# Pi2c.net
KiCad netlist of a schematic drawn in EAGLE
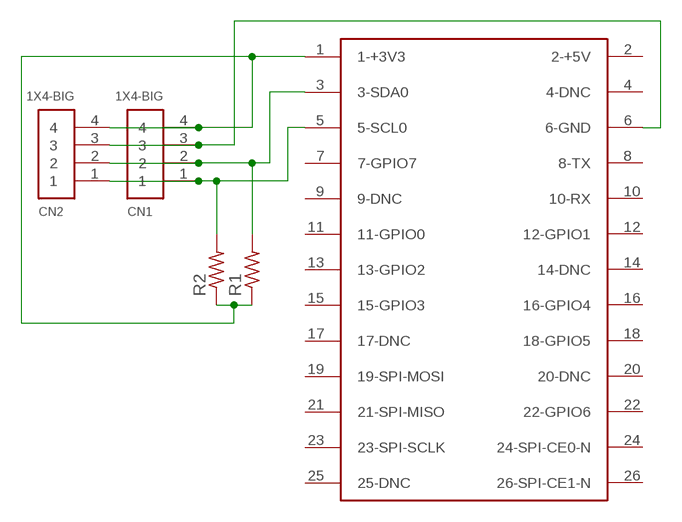
[diagram p0: schematic, sheet 1]

(export (version "E")
  (design (tool "Eeschema 10.0.6"))
  (components
    (comp (ref "CN1")
      (value "1X4-BIG")
      (footprint "eagle-import:1X04-BIG")
      (libsource (lib "eagle-import") (part "1X4-BIG"))
    )
    (comp (ref "CN2")
      (value "1X4-BIG")
      (footprint "eagle-import:1X04-BIG")
      (libsource (lib "eagle-import") (part "1X4-BIG"))
    )
    (comp (ref "R1")
      (value "R-US_0207/7")
      (footprint "eagle-import:0207_7")
      (libsource (lib "eagle-import") (part "R-US_0207/7"))
    )
    (comp (ref "R2")
      (value "R-US_0207/7")
      (footprint "eagle-import:0207_7")
      (libsource (lib "eagle-import") (part "R-US_0207/7"))
    )
    (comp (ref "U$1")
      (value "RASPBERRY-PI")
      (footprint "eagle-import:RASPBERRY-PI")
      (libsource (lib "eagle-import") (part "RASPBERRY-PI"))
    )
  )
  (nets
    (net (code "1") (name "Net-(U$1-1-+3V3)") (class "Default")
      (node (ref "CN1") (pin "4") (pinfunction "4_4") (pintype "bidirectional"))
      (node (ref "CN2") (pin "4") (pinfunction "4_4") (pintype "bidirectional"))
      (node (ref "R1") (pin "1") (pinfunction "1_1") (pintype "passive"))
      (node (ref "R2") (pin "1") (pinfunction "1_1") (pintype "passive"))
      (node (ref "U$1") (pin "1") (pinfunction "1-+3V3_1") (pintype "bidirectional"))
    )
    (net (code "2") (name "Net-(U$1-3-SDA0)") (class "Default")
      (node (ref "CN1") (pin "2") (pinfunction "2_2") (pintype "bidirectional"))
      (node (ref "CN2") (pin "2") (pinfunction "2_2") (pintype "bidirectional"))
      (node (ref "R1") (pin "2") (pinfunction "2_2") (pintype "passive"))
      (node (ref "U$1") (pin "3") (pinfunction "3-SDA0_3") (pintype "bidirectional"))
    )
    (net (code "3") (name "Net-(U$1-5-SCL0)") (class "Default")
      (node (ref "CN1") (pin "1") (pinfunction "1_1") (pintype "bidirectional"))
      (node (ref "CN2") (pin "1") (pinfunction "1_1") (pintype "bidirectional"))
      (node (ref "R2") (pin "2") (pinfunction "2_2") (pintype "passive"))
      (node (ref "U$1") (pin "5") (pinfunction "5-SCL0_5") (pintype "bidirectional"))
    )
    (net (code "4") (name "Net-(U$1-6-GND)") (class "Default")
      (node (ref "CN1") (pin "3") (pinfunction "3_3") (pintype "bidirectional"))
      (node (ref "CN2") (pin "3") (pinfunction "3_3") (pintype "bidirectional"))
      (node (ref "U$1") (pin "6") (pinfunction "6-GND_6") (pintype "bidirectional"))
    )
    (net (code "5") (name "unconnected-(U$1-2-+5V-Pad2)") (class "Default")
      (node (ref "U$1") (pin "2") (pinfunction "2-+5V_2") (pintype "bidirectional"))
    )
    (net (code "6") (name "unconnected-(U$1-4-DNC-Pad4)") (class "Default")
      (node (ref "U$1") (pin "4") (pinfunction "4-DNC_4") (pintype "bidirectional"))
    )
    (net (code "7") (name "unconnected-(U$1-7-GPIO7-Pad7)") (class "Default")
      (node (ref "U$1") (pin "7") (pinfunction "7-GPIO7_7") (pintype "bidirectional"))
    )
    (net (code "8") (name "unconnected-(U$1-8-TX-Pad8)") (class "Default")
      (node (ref "U$1") (pin "8") (pinfunction "8-TX_8") (pintype "bidirectional"))
    )
    (net (code "9") (name "unconnected-(U$1-9-DNC-Pad9)") (class "Default")
      (node (ref "U$1") (pin "9") (pinfunction "9-DNC_9") (pintype "bidirectional"))
    )
    (net (code "10") (name "unconnected-(U$1-10-RX-Pad10)") (class "Default")
      (node (ref "U$1") (pin "10") (pinfunction "10-RX_10") (pintype "bidirectional"))
    )
    (net (code "11") (name "unconnected-(U$1-11-GPIO0-Pad11)") (class "Default")
      (node (ref "U$1") (pin "11") (pinfunction "11-GPIO0_11") (pintype "bidirectional"))
    )
    (net (code "12") (name "unconnected-(U$1-12-GPIO1-Pad12)") (class "Default")
      (node (ref "U$1") (pin "12") (pinfunction "12-GPIO1_12") (pintype "bidirectional"))
    )
    (net (code "13") (name "unconnected-(U$1-13-GPIO2-Pad13)") (class "Default")
      (node (ref "U$1") (pin "13") (pinfunction "13-GPIO2_13") (pintype "bidirectional"))
    )
    (net (code "14") (name "unconnected-(U$1-14-DNC-Pad14)") (class "Default")
      (node (ref "U$1") (pin "14") (pinfunction "14-DNC_14") (pintype "bidirectional"))
    )
    (net (code "15") (name "unconnected-(U$1-15-GPIO3-Pad15)") (class "Default")
      (node (ref "U$1") (pin "15") (pinfunction "15-GPIO3_15") (pintype "bidirectional"))
    )
    (net (code "16") (name "unconnected-(U$1-16-GPIO4-Pad16)") (class "Default")
      (node (ref "U$1") (pin "16") (pinfunction "16-GPIO4_16") (pintype "bidirectional"))
    )
    (net (code "17") (name "unconnected-(U$1-17-DNC-Pad17)") (class "Default")
      (node (ref "U$1") (pin "17") (pinfunction "17-DNC_17") (pintype "bidirectional"))
    )
    (net (code "18") (name "unconnected-(U$1-18-GPIO5-Pad18)") (class "Default")
      (node (ref "U$1") (pin "18") (pinfunction "18-GPIO5_18") (pintype "bidirectional"))
    )
    (net (code "19") (name "unconnected-(U$1-19-SPI-MOSI-Pad19)") (class "Default")
      (node (ref "U$1") (pin "19") (pinfunction "19-SPI-MOSI_19") (pintype "bidirectional"))
    )
    (net (code "20") (name "unconnected-(U$1-20-DNC-Pad20)") (class "Default")
      (node (ref "U$1") (pin "20") (pinfunction "20-DNC_20") (pintype "bidirectional"))
    )
    (net (code "21") (name "unconnected-(U$1-21-SPI-MISO-Pad21)") (class "Default")
      (node (ref "U$1") (pin "21") (pinfunction "21-SPI-MISO_21") (pintype "bidirectional"))
    )
    (net (code "22") (name "unconnected-(U$1-22-GPIO6-Pad22)") (class "Default")
      (node (ref "U$1") (pin "22") (pinfunction "22-GPIO6_22") (pintype "bidirectional"))
    )
    (net (code "23") (name "unconnected-(U$1-23-SPI-SCLK-Pad23)") (class "Default")
      (node (ref "U$1") (pin "23") (pinfunction "23-SPI-SCLK_23") (pintype "bidirectional"))
    )
    (net (code "24") (name "unconnected-(U$1-24-SPI-CE0-N-Pad24)") (class "Default")
      (node (ref "U$1") (pin "24") (pinfunction "24-SPI-CE0-N_24") (pintype "bidirectional"))
    )
    (net (code "25") (name "unconnected-(U$1-25-DNC-Pad25)") (class "Default")
      (node (ref "U$1") (pin "25") (pinfunction "25-DNC_25") (pintype "bidirectional"))
    )
    (net (code "26") (name "unconnected-(U$1-26-SPI-CE1-N-Pad26)") (class "Default")
      (node (ref "U$1") (pin "26") (pinfunction "26-SPI-CE1-N_26") (pintype "bidirectional"))
    )
  )
)
